# supra.net
KiCad netlist of a schematic drawn in EAGLE
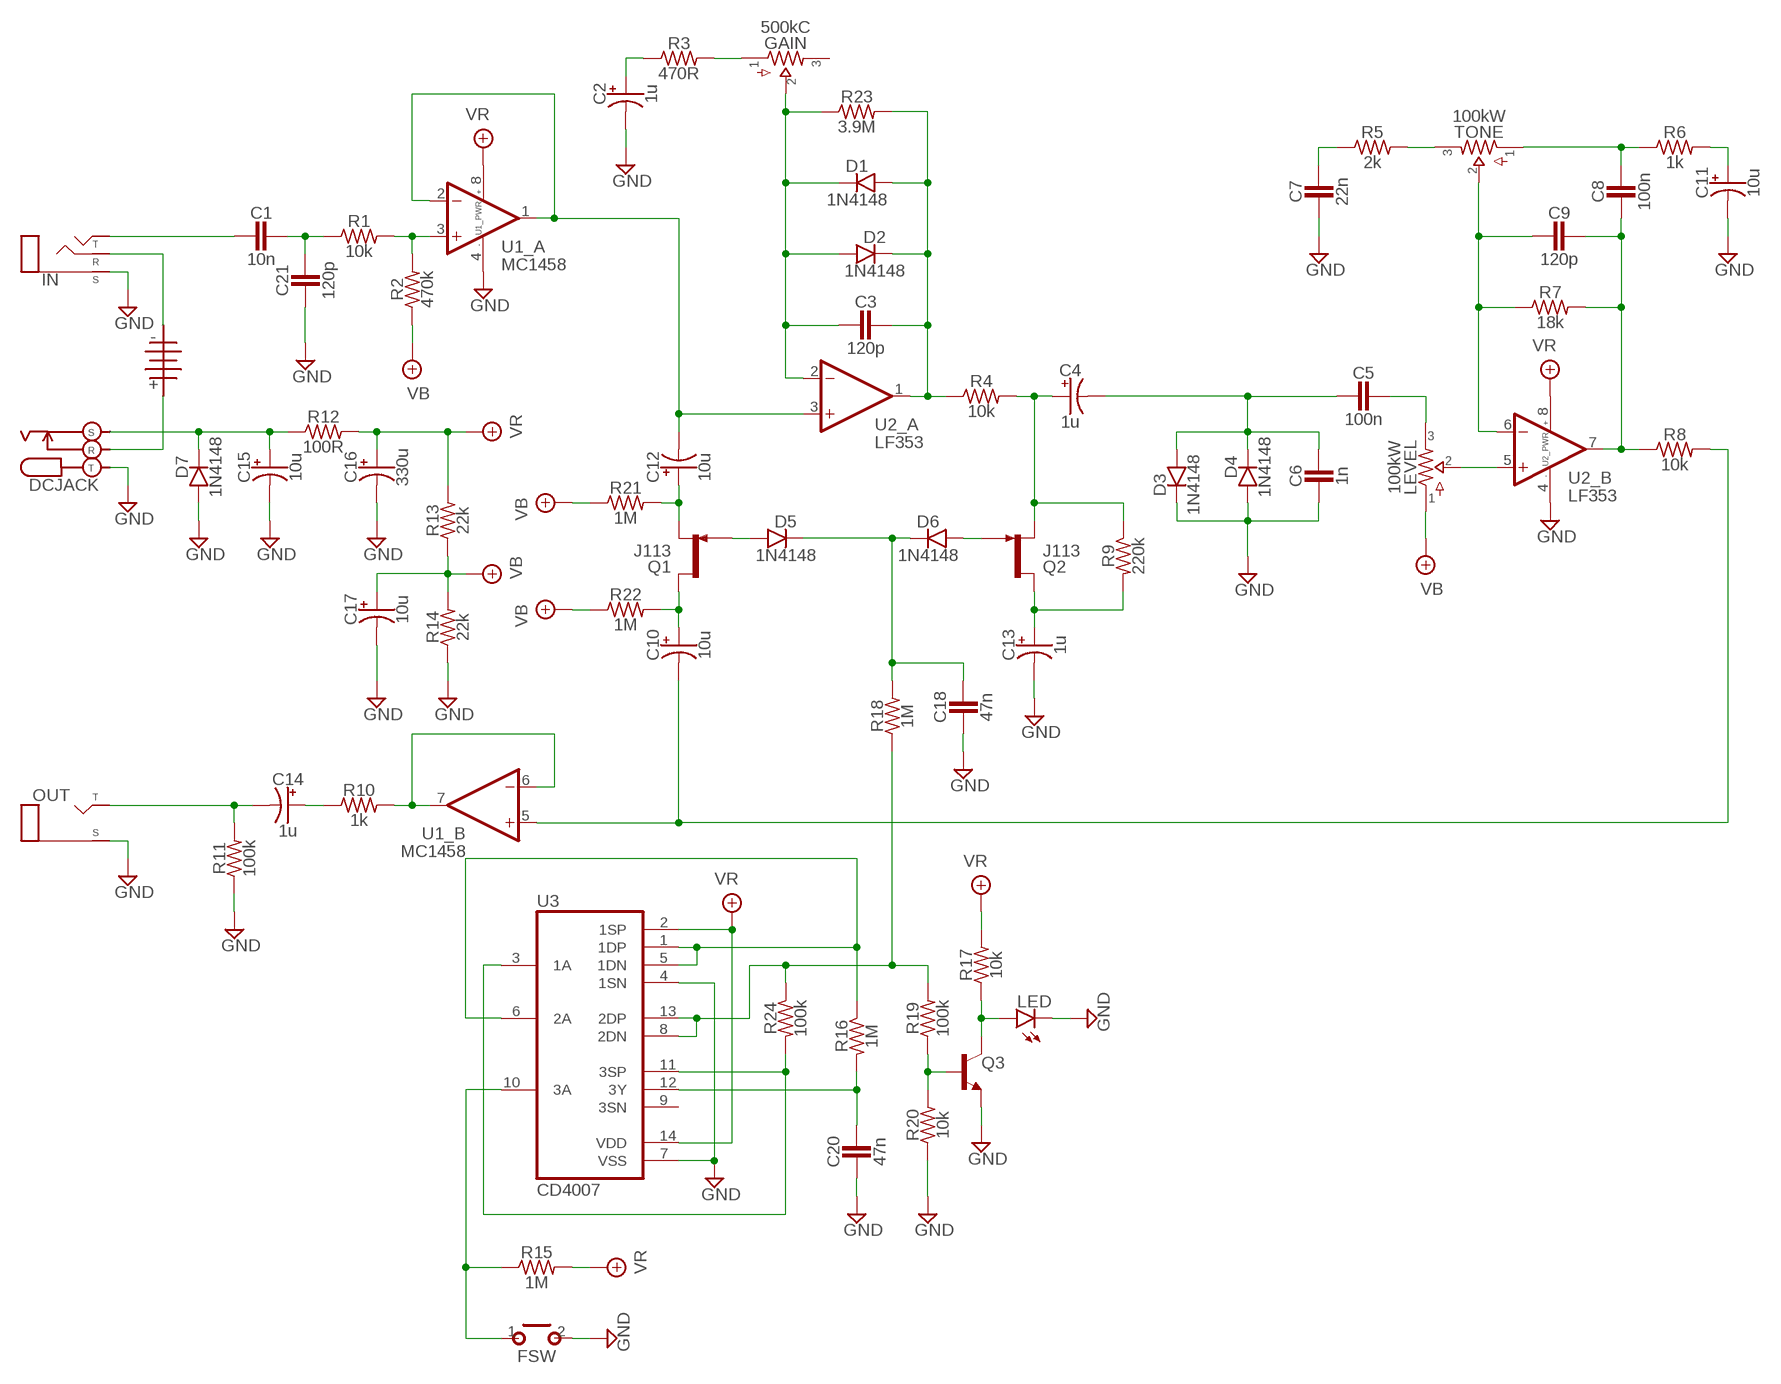
[diagram p0: schematic, sheet 1]

(export (version "E")
  (design (tool "Eeschema 10.0.6"))
  (components
    (comp (ref "1101")
      (value "BATTERY")
      (footprint "eagle-import:TWO_PADS")
      (libsource (lib "eagle-import") (part "BATTERY"))
    )
    (comp (ref "C1")
      (value "10n")
      (footprint "eagle-import:BOX_SMALL")
      (libsource (lib "eagle-import") (part "CER/FILMBOX.1"))
    )
    (comp (ref "C2")
      (value "1u")
      (footprint "eagle-import:050_020")
      (libsource (lib "eagle-import") (part "0500"))
    )
    (comp (ref "C3")
      (value "120p")
      (footprint "eagle-import:BOX_SMALL")
      (libsource (lib "eagle-import") (part "CER/FILMBOX.1"))
    )
    (comp (ref "C4")
      (value "1u")
      (footprint "eagle-import:050_020")
      (libsource (lib "eagle-import") (part "0500"))
    )
    (comp (ref "C5")
      (value "100n")
      (footprint "eagle-import:BOX_SMALL")
      (libsource (lib "eagle-import") (part "CER/FILMBOX.1"))
    )
    (comp (ref "C6")
      (value "1n")
      (footprint "eagle-import:BOX_SMALL")
      (libsource (lib "eagle-import") (part "CER/FILMBOX.1"))
    )
    (comp (ref "C7")
      (value "22n")
      (footprint "eagle-import:BOX_SMALL")
      (libsource (lib "eagle-import") (part "CER/FILMBOX.1"))
    )
    (comp (ref "C8")
      (value "100n")
      (footprint "eagle-import:BOX_SMALL")
      (libsource (lib "eagle-import") (part "CER/FILMBOX.1"))
    )
    (comp (ref "C9")
      (value "120p")
      (footprint "eagle-import:BOX_SMALL")
      (libsource (lib "eagle-import") (part "CER/FILMBOX.1"))
    )
    (comp (ref "C10")
      (value "10u")
      (footprint "eagle-import:050_020")
      (libsource (lib "eagle-import") (part "0500"))
    )
    (comp (ref "C11")
      (value "10u")
      (footprint "eagle-import:050_020")
      (libsource (lib "eagle-import") (part "0500"))
    )
    (comp (ref "C12")
      (value "10u")
      (footprint "eagle-import:050_020")
      (libsource (lib "eagle-import") (part "0500"))
    )
    (comp (ref "C13")
      (value "1u")
      (footprint "eagle-import:050_020")
      (libsource (lib "eagle-import") (part "0500"))
    )
    (comp (ref "C14")
      (value "1u")
      (footprint "eagle-import:050_020")
      (libsource (lib "eagle-import") (part "0500"))
    )
    (comp (ref "C15")
      (value "10u")
      (footprint "eagle-import:050_020")
      (libsource (lib "eagle-import") (part "0500"))
    )
    (comp (ref "C16")
      (value "330u")
      (footprint "eagle-import:050_020")
      (libsource (lib "eagle-import") (part "0500"))
    )
    (comp (ref "C17")
      (value "10u")
      (footprint "eagle-import:050_020")
      (libsource (lib "eagle-import") (part "0500"))
    )
    (comp (ref "C18")
      (value "47n")
      (footprint "eagle-import:BOX_SMALL")
      (libsource (lib "eagle-import") (part "CER/FILMBOX.1"))
    )
    (comp (ref "C20")
      (value "47n")
      (footprint "eagle-import:BOX_SMALL")
      (libsource (lib "eagle-import") (part "CER/FILMBOX.1"))
    )
    (comp (ref "C21")
      (value "120p")
      (footprint "eagle-import:BOX_SMALL")
      (libsource (lib "eagle-import") (part "CER/FILMBOX.1"))
    )
    (comp (ref "D1")
      (value "1N4148")
      (footprint "eagle-import:DO35-2")
      (libsource (lib "eagle-import") (part "DO35.2"))
    )
    (comp (ref "D2")
      (value "1N4148")
      (footprint "eagle-import:DO35-2")
      (libsource (lib "eagle-import") (part "DO35.2"))
    )
    (comp (ref "D3")
      (value "1N4148")
      (footprint "eagle-import:DO35-2")
      (libsource (lib "eagle-import") (part "DO35.2"))
    )
    (comp (ref "D4")
      (value "1N4148")
      (footprint "eagle-import:DO35-2")
      (libsource (lib "eagle-import") (part "DO35.2"))
    )
    (comp (ref "D5")
      (value "1N4148")
      (footprint "eagle-import:DO35-2")
      (libsource (lib "eagle-import") (part "DO35.2"))
    )
    (comp (ref "D6")
      (value "1N4148")
      (footprint "eagle-import:DO35-2")
      (libsource (lib "eagle-import") (part "DO35.2"))
    )
    (comp (ref "D7")
      (value "1N4148")
      (footprint "eagle-import:DO35-2")
      (libsource (lib "eagle-import") (part "DO35.2"))
    )
    (comp (ref "DCJACK")
      (value "DC_KOBICONN")
      (footprint "eagle-import:DC_KOBICONN")
      (libsource (lib "eagle-import") (part "DC_KOBICONN"))
    )
    (comp (ref "FSW")
      (value "MOMENTARY")
      (footprint "eagle-import:SPST")
      (libsource (lib "eagle-import") (part "MOMENTARY"))
    )
    (comp (ref "GAIN")
      (value "500kC")
      (footprint "eagle-import:16MM")
      (libsource (lib "eagle-import") (part "POTS16MM"))
    )
    (comp (ref "IN")
      (value "STEREO")
      (footprint "eagle-import:STEREO_PCB")
      (libsource (lib "eagle-import") (part "STEREO"))
    )
    (comp (ref "LED")
      (value "LED")
      (footprint "eagle-import:3MM_D")
      (libsource (lib "eagle-import") (part "LED"))
    )
    (comp (ref "LEVEL")
      (value "100kW")
      (footprint "eagle-import:16MM")
      (libsource (lib "eagle-import") (part "POTS16MM"))
    )
    (comp (ref "OUT")
      (value "MONO")
      (footprint "eagle-import:TWO_PADS")
      (libsource (lib "eagle-import") (part "MONO"))
    )
    (comp (ref "Q1")
      (value "J113")
      (footprint "eagle-import:TO92-")
      (libsource (lib "eagle-import") (part "2N5457"))
    )
    (comp (ref "Q2")
      (value "J113")
      (footprint "eagle-import:TO92-")
      (libsource (lib "eagle-import") (part "2N5457"))
    )
    (comp (ref "Q3")
      (value "2N3904")
      (footprint "eagle-import:TO92-")
      (libsource (lib "eagle-import") (part "2N3904"))
    )
    (comp (ref "R1")
      (value "10k")
      (footprint "eagle-import:R0207_3")
      (libsource (lib "eagle-import") (part "R_.3B"))
    )
    (comp (ref "R2")
      (value "470k")
      (footprint "eagle-import:R0207_3")
      (libsource (lib "eagle-import") (part "R_.3B"))
    )
    (comp (ref "R3")
      (value "470R")
      (footprint "eagle-import:R0207_3")
      (libsource (lib "eagle-import") (part "R_.3B"))
    )
    (comp (ref "R4")
      (value "10k")
      (footprint "eagle-import:R0207_3")
      (libsource (lib "eagle-import") (part "R_.3B"))
    )
    (comp (ref "R5")
      (value "2k")
      (footprint "eagle-import:R0207_3")
      (libsource (lib "eagle-import") (part "R_.3B"))
    )
    (comp (ref "R6")
      (value "1k")
      (footprint "eagle-import:R0207_3")
      (libsource (lib "eagle-import") (part "R_.3B"))
    )
    (comp (ref "R7")
      (value "18k")
      (footprint "eagle-import:R0207_3")
      (libsource (lib "eagle-import") (part "R_.3B"))
    )
    (comp (ref "R8")
      (value "10k")
      (footprint "eagle-import:R0207_3")
      (libsource (lib "eagle-import") (part "R_.3B"))
    )
    (comp (ref "R9")
      (value "220k")
      (footprint "eagle-import:R0207_3")
      (libsource (lib "eagle-import") (part "R_.3B"))
    )
    (comp (ref "R10")
      (value "1k")
      (footprint "eagle-import:R0207_3")
      (libsource (lib "eagle-import") (part "R_.3B"))
    )
    (comp (ref "R11")
      (value "100k")
      (footprint "eagle-import:R0207_3")
      (libsource (lib "eagle-import") (part "R_.3B"))
    )
    (comp (ref "R12")
      (value "100R")
      (footprint "eagle-import:R0207_3")
      (libsource (lib "eagle-import") (part "R_.3B"))
    )
    (comp (ref "R13")
      (value "22k")
      (footprint "eagle-import:R0207_3")
      (libsource (lib "eagle-import") (part "R_.3B"))
    )
    (comp (ref "R14")
      (value "22k")
      (footprint "eagle-import:R0207_3")
      (libsource (lib "eagle-import") (part "R_.3B"))
    )
    (comp (ref "R15")
      (value "1M")
      (footprint "eagle-import:R0207_3")
      (libsource (lib "eagle-import") (part "R_.3B"))
    )
    (comp (ref "R16")
      (value "1M")
      (footprint "eagle-import:R0207_3")
      (libsource (lib "eagle-import") (part "R_.3B"))
    )
    (comp (ref "R17")
      (value "10k")
      (footprint "eagle-import:R0207_3")
      (libsource (lib "eagle-import") (part "R_.3B"))
    )
    (comp (ref "R18")
      (value "1M")
      (footprint "eagle-import:R0207_3")
      (libsource (lib "eagle-import") (part "R_.3B"))
    )
    (comp (ref "R19")
      (value "100k")
      (footprint "eagle-import:R0207_3")
      (libsource (lib "eagle-import") (part "R_.3B"))
    )
    (comp (ref "R20")
      (value "10k")
      (footprint "eagle-import:R0207_3")
      (libsource (lib "eagle-import") (part "R_.3B"))
    )
    (comp (ref "R21")
      (value "1M")
      (footprint "eagle-import:R0207_3")
      (libsource (lib "eagle-import") (part "R_.3B"))
    )
    (comp (ref "R22")
      (value "1M")
      (footprint "eagle-import:R0207_3")
      (libsource (lib "eagle-import") (part "R_.3B"))
    )
    (comp (ref "R23")
      (value "3.9M")
      (footprint "eagle-import:R0207_3")
      (libsource (lib "eagle-import") (part "R_.3B"))
    )
    (comp (ref "R24")
      (value "100k")
      (footprint "eagle-import:R0207_3")
      (libsource (lib "eagle-import") (part "R_.3B"))
    )
    (comp (ref "TONE")
      (value "100kW")
      (footprint "eagle-import:16MM")
      (libsource (lib "eagle-import") (part "POTS16MM"))
    )
    (comp (ref "U1")
      (value "MC1458")
      (footprint "eagle-import:DIL0")
      (libsource (lib "eagle-import") (part "DUALTH"))
    )
    (comp (ref "U2")
      (value "LF353")
      (footprint "eagle-import:DIL0")
      (libsource (lib "eagle-import") (part "DUALTH"))
    )
    (comp (ref "U3")
      (value "CD4007")
      (footprint "eagle-import:DIL14")
      (libsource (lib "eagle-import") (part "4007N"))
    )
  )
  (nets
    (net (code "1") (name "GND") (class "Default")
      (node (ref "C11") (pin "-") (pinfunction "-_-") (pintype "passive"))
      (node (ref "C13") (pin "-") (pinfunction "-_-") (pintype "passive"))
      (node (ref "C15") (pin "-") (pinfunction "-_-") (pintype "passive"))
      (node (ref "C16") (pin "-") (pinfunction "-_-") (pintype "passive"))
      (node (ref "C17") (pin "-") (pinfunction "-_-") (pintype "passive"))
      (node (ref "C18") (pin "2") (pinfunction "2_2") (pintype "passive"))
      (node (ref "C2") (pin "-") (pinfunction "-_-") (pintype "passive"))
      (node (ref "C20") (pin "2") (pinfunction "2_2") (pintype "passive"))
      (node (ref "C21") (pin "2") (pinfunction "2_2") (pintype "passive"))
      (node (ref "C6") (pin "2") (pinfunction "2_2") (pintype "passive"))
      (node (ref "C7") (pin "2") (pinfunction "2_2") (pintype "passive"))
      (node (ref "D3") (pin "C") (pinfunction "C_C") (pintype "passive"))
      (node (ref "D4") (pin "A") (pinfunction "A_A") (pintype "passive"))
      (node (ref "D7") (pin "A") (pinfunction "A_A") (pintype "passive"))
      (node (ref "DCJACK") (pin "T") (pinfunction "T_T") (pintype "bidirectional"))
      (node (ref "FSW") (pin "2") (pinfunction "S_2") (pintype "passive"))
      (node (ref "IN") (pin "P$1") (pinfunction "S_P$1") (pintype "passive"))
      (node (ref "LED") (pin "P$1") (pinfunction "C_P$1") (pintype "passive"))
      (node (ref "OUT") (pin "S") (pinfunction "SLEEVE_S") (pintype "passive"))
      (node (ref "Q3") (pin "3") (pinfunction "E_3") (pintype "passive"))
      (node (ref "R11") (pin "1") (pinfunction "1_1") (pintype "passive"))
      (node (ref "R14") (pin "1") (pinfunction "1_1") (pintype "passive"))
      (node (ref "R20") (pin "1") (pinfunction "1_1") (pintype "passive"))
      (node (ref "U1") (pin "4") (pinfunction "V-_4") (pintype "power_in"))
      (node (ref "U2") (pin "4") (pinfunction "V-_4") (pintype "power_in"))
      (node (ref "U3") (pin "4") (pinfunction "1SN_4") (pintype "open_collector"))
      (node (ref "U3") (pin "7") (pinfunction "VSS_7") (pintype "input"))
    )
    (net (code "2") (name "Net-(1101-P$1)") (class "Default")
      (node (ref "1101") (pin "T") (pinfunction "P$1_T") (pintype "bidirectional"))
      (node (ref "DCJACK") (pin "R") (pinfunction "R_R") (pintype "bidirectional"))
    )
    (net (code "3") (name "Net-(1101-P$2)") (class "Default")
      (node (ref "1101") (pin "S") (pinfunction "P$2_S") (pintype "bidirectional"))
      (node (ref "IN") (pin "P$2") (pinfunction "R_P$2") (pintype "passive"))
    )
    (net (code "4") (name "Net-(C1-Pad1)") (class "Default")
      (node (ref "C1") (pin "1") (pinfunction "1_1") (pintype "passive"))
      (node (ref "C21") (pin "1") (pinfunction "1_1") (pintype "passive"))
      (node (ref "R1") (pin "1") (pinfunction "1_1") (pintype "passive"))
    )
    (net (code "5") (name "Net-(C2-Pad+)") (class "Default")
      (node (ref "C2") (pin "+") (pinfunction "+_+") (pintype "passive"))
      (node (ref "R3") (pin "1") (pinfunction "1_1") (pintype "passive"))
    )
    (net (code "6") (name "Net-(C4-Pad-)") (class "Default")
      (node (ref "C4") (pin "-") (pinfunction "-_-") (pintype "passive"))
      (node (ref "C5") (pin "2") (pinfunction "2_2") (pintype "passive"))
      (node (ref "C6") (pin "1") (pinfunction "1_1") (pintype "passive"))
      (node (ref "D3") (pin "A") (pinfunction "A_A") (pintype "passive"))
      (node (ref "D4") (pin "C") (pinfunction "C_C") (pintype "passive"))
    )
    (net (code "7") (name "Net-(C5-Pad1)") (class "Default")
      (node (ref "C5") (pin "1") (pinfunction "1_1") (pintype "passive"))
      (node (ref "LEVEL") (pin "3") (pinfunction "3_3") (pintype "passive"))
    )
    (net (code "8") (name "Net-(C7-Pad1)") (class "Default")
      (node (ref "C7") (pin "1") (pinfunction "1_1") (pintype "passive"))
      (node (ref "R5") (pin "1") (pinfunction "1_1") (pintype "passive"))
    )
    (net (code "9") (name "Net-(C8-Pad1)") (class "Default")
      (node (ref "C8") (pin "1") (pinfunction "1_1") (pintype "passive"))
      (node (ref "R6") (pin "1") (pinfunction "1_1") (pintype "passive"))
      (node (ref "TONE") (pin "1") (pinfunction "1_1") (pintype "passive"))
    )
    (net (code "10") (name "Net-(C11-Pad+)") (class "Default")
      (node (ref "C11") (pin "+") (pinfunction "+_+") (pintype "passive"))
      (node (ref "R6") (pin "2") (pinfunction "2_2") (pintype "passive"))
    )
    (net (code "11") (name "Net-(C14-Pad+)") (class "Default")
      (node (ref "C14") (pin "+") (pinfunction "+_+") (pintype "passive"))
      (node (ref "R10") (pin "1") (pinfunction "1_1") (pintype "passive"))
    )
    (net (code "12") (name "Net-(C15-Pad+)") (class "Default")
      (node (ref "C15") (pin "+") (pinfunction "+_+") (pintype "passive"))
      (node (ref "D7") (pin "C") (pinfunction "C_C") (pintype "passive"))
      (node (ref "DCJACK") (pin "S") (pinfunction "S_S") (pintype "bidirectional"))
      (node (ref "R12") (pin "1") (pinfunction "1_1") (pintype "passive"))
    )
    (net (code "13") (name "Net-(C18-Pad1)") (class "Default")
      (node (ref "C18") (pin "1") (pinfunction "1_1") (pintype "passive"))
      (node (ref "D5") (pin "C") (pinfunction "C_C") (pintype "passive"))
      (node (ref "D6") (pin "C") (pinfunction "C_C") (pintype "passive"))
      (node (ref "R18") (pin "2") (pinfunction "2_2") (pintype "passive"))
    )
    (net (code "14") (name "Net-(FSW-P)") (class "Default")
      (node (ref "FSW") (pin "1") (pinfunction "P_1") (pintype "passive"))
      (node (ref "R15") (pin "1") (pinfunction "1_1") (pintype "passive"))
      (node (ref "U3") (pin "10") (pinfunction "3A_10") (pintype "input"))
    )
    (net (code "15") (name "Net-(GAIN-Pad1)") (class "Default")
      (node (ref "GAIN") (pin "1") (pinfunction "1_1") (pintype "passive"))
      (node (ref "R3") (pin "2") (pinfunction "2_2") (pintype "passive"))
    )
    (net (code "16") (name "Net-(IN-T)") (class "Default")
      (node (ref "C1") (pin "2") (pinfunction "2_2") (pintype "passive"))
      (node (ref "IN") (pin "P$3") (pinfunction "T_P$3") (pintype "passive"))
    )
    (net (code "17") (name "Net-(LED-A)") (class "Default")
      (node (ref "LED") (pin "ANODE") (pinfunction "A_ANODE") (pintype "passive"))
      (node (ref "Q3") (pin "1") (pinfunction "C_1") (pintype "passive"))
      (node (ref "R17") (pin "1") (pinfunction "1_1") (pintype "passive"))
    )
    (net (code "18") (name "Net-(OUT-TIP)") (class "Default")
      (node (ref "C14") (pin "-") (pinfunction "-_-") (pintype "passive"))
      (node (ref "OUT") (pin "T") (pinfunction "TIP_T") (pintype "passive"))
      (node (ref "R11") (pin "2") (pinfunction "2_2") (pintype "passive"))
    )
    (net (code "19") (name "Net-(Q1-D)") (class "Default")
      (node (ref "C10") (pin "+") (pinfunction "+_+") (pintype "passive"))
      (node (ref "Q1") (pin "3") (pinfunction "D_3") (pintype "passive"))
      (node (ref "R22") (pin "2") (pinfunction "2_2") (pintype "passive"))
    )
    (net (code "20") (name "Net-(Q1-G)") (class "Default")
      (node (ref "D5") (pin "A") (pinfunction "A_A") (pintype "passive"))
      (node (ref "Q1") (pin "1") (pinfunction "G_1") (pintype "passive"))
    )
    (net (code "21") (name "Net-(Q1-S)") (class "Default")
      (node (ref "C12") (pin "+") (pinfunction "+_+") (pintype "passive"))
      (node (ref "Q1") (pin "2") (pinfunction "S_2") (pintype "passive"))
      (node (ref "R21") (pin "2") (pinfunction "2_2") (pintype "passive"))
    )
    (net (code "22") (name "Net-(Q2-D)") (class "Default")
      (node (ref "C13") (pin "+") (pinfunction "+_+") (pintype "passive"))
      (node (ref "Q2") (pin "3") (pinfunction "D_3") (pintype "passive"))
      (node (ref "R9") (pin "2") (pinfunction "2_2") (pintype "passive"))
    )
    (net (code "23") (name "Net-(Q2-G)") (class "Default")
      (node (ref "D6") (pin "A") (pinfunction "A_A") (pintype "passive"))
      (node (ref "Q2") (pin "1") (pinfunction "G_1") (pintype "passive"))
    )
    (net (code "24") (name "Net-(Q2-S)") (class "Default")
      (node (ref "C4") (pin "+") (pinfunction "+_+") (pintype "passive"))
      (node (ref "Q2") (pin "2") (pinfunction "S_2") (pintype "passive"))
      (node (ref "R4") (pin "2") (pinfunction "2_2") (pintype "passive"))
      (node (ref "R9") (pin "1") (pinfunction "1_1") (pintype "passive"))
    )
    (net (code "25") (name "Net-(Q3-B)") (class "Default")
      (node (ref "Q3") (pin "2") (pinfunction "B_2") (pintype "passive"))
      (node (ref "R19") (pin "1") (pinfunction "1_1") (pintype "passive"))
      (node (ref "R20") (pin "2") (pinfunction "2_2") (pintype "passive"))
    )
    (net (code "26") (name "Net-(R5-Pad2)") (class "Default")
      (node (ref "R5") (pin "2") (pinfunction "2_2") (pintype "passive"))
      (node (ref "TONE") (pin "3") (pinfunction "3_3") (pintype "passive"))
    )
    (net (code "27") (name "Net-(U1A-+IN)") (class "Default")
      (node (ref "R1") (pin "2") (pinfunction "2_2") (pintype "passive"))
      (node (ref "R2") (pin "2") (pinfunction "2_2") (pintype "passive"))
      (node (ref "U1") (pin "3") (pinfunction "+IN_3") (pintype "input"))
    )
    (net (code "28") (name "Net-(U1A--IN)") (class "Default")
      (node (ref "C12") (pin "-") (pinfunction "-_-") (pintype "passive"))
      (node (ref "U1") (pin "1") (pinfunction "OUT_1") (pintype "output"))
      (node (ref "U1") (pin "2") (pinfunction "-IN_2") (pintype "input"))
      (node (ref "U2") (pin "3") (pinfunction "+IN_3") (pintype "input"))
    )
    (net (code "29") (name "Net-(U1B-+IN)") (class "Default")
      (node (ref "C10") (pin "-") (pinfunction "-_-") (pintype "passive"))
      (node (ref "R8") (pin "2") (pinfunction "2_2") (pintype "passive"))
      (node (ref "U1") (pin "5") (pinfunction "+IN_5") (pintype "input"))
    )
    (net (code "30") (name "Net-(U1B--IN)") (class "Default")
      (node (ref "R10") (pin "2") (pinfunction "2_2") (pintype "passive"))
      (node (ref "U1") (pin "6") (pinfunction "-IN_6") (pintype "input"))
      (node (ref "U1") (pin "7") (pinfunction "OUT_7") (pintype "output"))
    )
    (net (code "31") (name "Net-(U2A--IN)") (class "Default")
      (node (ref "C3") (pin "2") (pinfunction "2_2") (pintype "passive"))
      (node (ref "D1") (pin "C") (pinfunction "C_C") (pintype "passive"))
      (node (ref "D2") (pin "A") (pinfunction "A_A") (pintype "passive"))
      (node (ref "GAIN") (pin "2") (pinfunction "2_2") (pintype "passive"))
      (node (ref "R23") (pin "1") (pinfunction "1_1") (pintype "passive"))
      (node (ref "U2") (pin "2") (pinfunction "-IN_2") (pintype "input"))
    )
    (net (code "32") (name "Net-(U2A-OUT)") (class "Default")
      (node (ref "C3") (pin "1") (pinfunction "1_1") (pintype "passive"))
      (node (ref "D1") (pin "A") (pinfunction "A_A") (pintype "passive"))
      (node (ref "D2") (pin "C") (pinfunction "C_C") (pintype "passive"))
      (node (ref "R23") (pin "2") (pinfunction "2_2") (pintype "passive"))
      (node (ref "R4") (pin "1") (pinfunction "1_1") (pintype "passive"))
      (node (ref "U2") (pin "1") (pinfunction "OUT_1") (pintype "output"))
    )
    (net (code "33") (name "Net-(U2B-+IN)") (class "Default")
      (node (ref "LEVEL") (pin "2") (pinfunction "2_2") (pintype "passive"))
      (node (ref "U2") (pin "5") (pinfunction "+IN_5") (pintype "input"))
    )
    (net (code "34") (name "Net-(U2B--IN)") (class "Default")
      (node (ref "C9") (pin "2") (pinfunction "2_2") (pintype "passive"))
      (node (ref "R7") (pin "1") (pinfunction "1_1") (pintype "passive"))
      (node (ref "TONE") (pin "2") (pinfunction "2_2") (pintype "passive"))
      (node (ref "U2") (pin "6") (pinfunction "-IN_6") (pintype "input"))
    )
    (net (code "35") (name "Net-(U2B-OUT)") (class "Default")
      (node (ref "C8") (pin "2") (pinfunction "2_2") (pintype "passive"))
      (node (ref "C9") (pin "1") (pinfunction "1_1") (pintype "passive"))
      (node (ref "R7") (pin "2") (pinfunction "2_2") (pintype "passive"))
      (node (ref "R8") (pin "1") (pinfunction "1_1") (pintype "passive"))
      (node (ref "U2") (pin "7") (pinfunction "OUT_7") (pintype "output"))
    )
    (net (code "36") (name "Net-(U3-1A)") (class "Default")
      (node (ref "R24") (pin "2") (pinfunction "2_2") (pintype "passive"))
      (node (ref "U3") (pin "11") (pinfunction "3SP_11") (pintype "bidirectional"))
      (node (ref "U3") (pin "3") (pinfunction "1A_3") (pintype "input"))
    )
    (net (code "37") (name "Net-(U3-1DN)") (class "Default")
      (node (ref "R16") (pin "1") (pinfunction "1_1") (pintype "passive"))
      (node (ref "U3") (pin "1") (pinfunction "1DP_1") (pintype "open_collector"))
      (node (ref "U3") (pin "5") (pinfunction "1DN_5") (pintype "open_collector"))
      (node (ref "U3") (pin "6") (pinfunction "2A_6") (pintype "input"))
    )
    (net (code "38") (name "Net-(U3-2DN)") (class "Default")
      (node (ref "R18") (pin "1") (pinfunction "1_1") (pintype "passive"))
      (node (ref "R19") (pin "2") (pinfunction "2_2") (pintype "passive"))
      (node (ref "R24") (pin "1") (pinfunction "1_1") (pintype "passive"))
      (node (ref "U3") (pin "13") (pinfunction "2DP_13") (pintype "bidirectional"))
      (node (ref "U3") (pin "8") (pinfunction "2DN_8") (pintype "bidirectional"))
    )
    (net (code "39") (name "Net-(U3-3Y)") (class "Default")
      (node (ref "C20") (pin "1") (pinfunction "1_1") (pintype "passive"))
      (node (ref "R16") (pin "2") (pinfunction "2_2") (pintype "passive"))
      (node (ref "U3") (pin "12") (pinfunction "3Y_12") (pintype "bidirectional"))
    )
    (net (code "40") (name "VB") (class "Default")
      (node (ref "C17") (pin "+") (pinfunction "+_+") (pintype "passive"))
      (node (ref "LEVEL") (pin "1") (pinfunction "1_1") (pintype "passive"))
      (node (ref "R13") (pin "1") (pinfunction "1_1") (pintype "passive"))
      (node (ref "R14") (pin "2") (pinfunction "2_2") (pintype "passive"))
      (node (ref "R2") (pin "1") (pinfunction "1_1") (pintype "passive"))
      (node (ref "R21") (pin "1") (pinfunction "1_1") (pintype "passive"))
      (node (ref "R22") (pin "1") (pinfunction "1_1") (pintype "passive"))
    )
    (net (code "41") (name "VR") (class "Default")
      (node (ref "C16") (pin "+") (pinfunction "+_+") (pintype "passive"))
      (node (ref "R12") (pin "2") (pinfunction "2_2") (pintype "passive"))
      (node (ref "R13") (pin "2") (pinfunction "2_2") (pintype "passive"))
      (node (ref "R15") (pin "2") (pinfunction "2_2") (pintype "passive"))
      (node (ref "R17") (pin "2") (pinfunction "2_2") (pintype "passive"))
      (node (ref "U1") (pin "8") (pinfunction "V+_8") (pintype "power_in"))
      (node (ref "U2") (pin "8") (pinfunction "V+_8") (pintype "power_in"))
      (node (ref "U3") (pin "14") (pinfunction "VDD_14") (pintype "input"))
      (node (ref "U3") (pin "2") (pinfunction "1SP_2") (pintype "open_collector"))
    )
    (net (code "42") (name "unconnected-(GAIN-Pad3)") (class "Default")
      (node (ref "GAIN") (pin "3") (pinfunction "3_3") (pintype "passive"))
    )
    (net (code "43") (name "unconnected-(U3-3SN-Pad9)") (class "Default")
      (node (ref "U3") (pin "9") (pinfunction "3SN_9") (pintype "bidirectional"))
    )
  )
)
